# bbr18_motor_battery_connection_board.net
KiCad netlist of a schematic drawn in Altium Designer
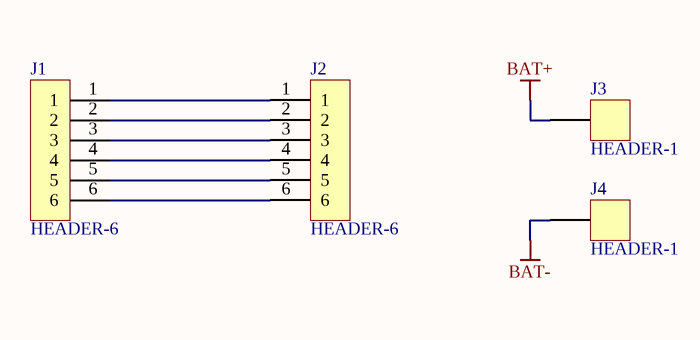
[diagram p0: bbr18_motor_battery_connection_board.SchDoc]

(export (version "E")
  (design (tool "Eeschema 10.0.6"))
  (components
    (comp (ref "J1")
      (value "HEADER-6")
      (footprint "MICRO-MATCH-FOB-06")
      (libsource (lib "connectors_micromatch") (part "HEADER-6"))
    )
    (comp (ref "J2")
      (value "HEADER-6")
      (footprint "MICRO-MATCH-FOB-06")
      (libsource (lib "") (part "HEADER-6_1"))
    )
    (comp (ref "J3")
      (value "HEADER-1")
      (footprint "2MM-BANANA-VIA")
      (libsource (lib "connectors") (part "HEADER-1"))
    )
    (comp (ref "J4")
      (value "HEADER-1")
      (footprint "2MM-BANANA-VIA")
      (libsource (lib "connectors") (part "HEADER-1"))
    )
  )
  (nets
    (net (code "1") (name "BAT+") (class "Default")
      (node (ref "J3") (pin "1") (pinfunction "1_1") (pintype "passive"))
    )
    (net (code "2") (name "BAT-") (class "Default")
      (node (ref "J4") (pin "1") (pinfunction "1_1") (pintype "passive"))
    )
    (net (code "3") (name "Net-(J1-Pad1)") (class "Default")
      (node (ref "J1") (pin "1") (pinfunction "1_1") (pintype "passive"))
      (node (ref "J2") (pin "1") (pinfunction "1_1") (pintype "passive"))
    )
    (net (code "4") (name "Net-(J1-Pad2)") (class "Default")
      (node (ref "J1") (pin "2") (pinfunction "2_2") (pintype "passive"))
      (node (ref "J2") (pin "2") (pinfunction "2_2") (pintype "passive"))
    )
    (net (code "5") (name "Net-(J1-Pad3)") (class "Default")
      (node (ref "J1") (pin "3") (pinfunction "3_3") (pintype "passive"))
      (node (ref "J2") (pin "3") (pinfunction "3_3") (pintype "passive"))
    )
    (net (code "6") (name "Net-(J1-Pad4)") (class "Default")
      (node (ref "J1") (pin "4") (pinfunction "4_4") (pintype "passive"))
      (node (ref "J2") (pin "4") (pinfunction "4_4") (pintype "passive"))
    )
    (net (code "7") (name "Net-(J1-Pad5)") (class "Default")
      (node (ref "J1") (pin "5") (pinfunction "5_5") (pintype "passive"))
      (node (ref "J2") (pin "5") (pinfunction "5_5") (pintype "passive"))
    )
    (net (code "8") (name "Net-(J1-Pad6)") (class "Default")
      (node (ref "J1") (pin "6") (pinfunction "6_6") (pintype "passive"))
      (node (ref "J2") (pin "6") (pinfunction "6_6") (pintype "passive"))
    )
  )
)
